# 02_LP_FMC.net
KiCad netlist of a schematic drawn in Altium Designer
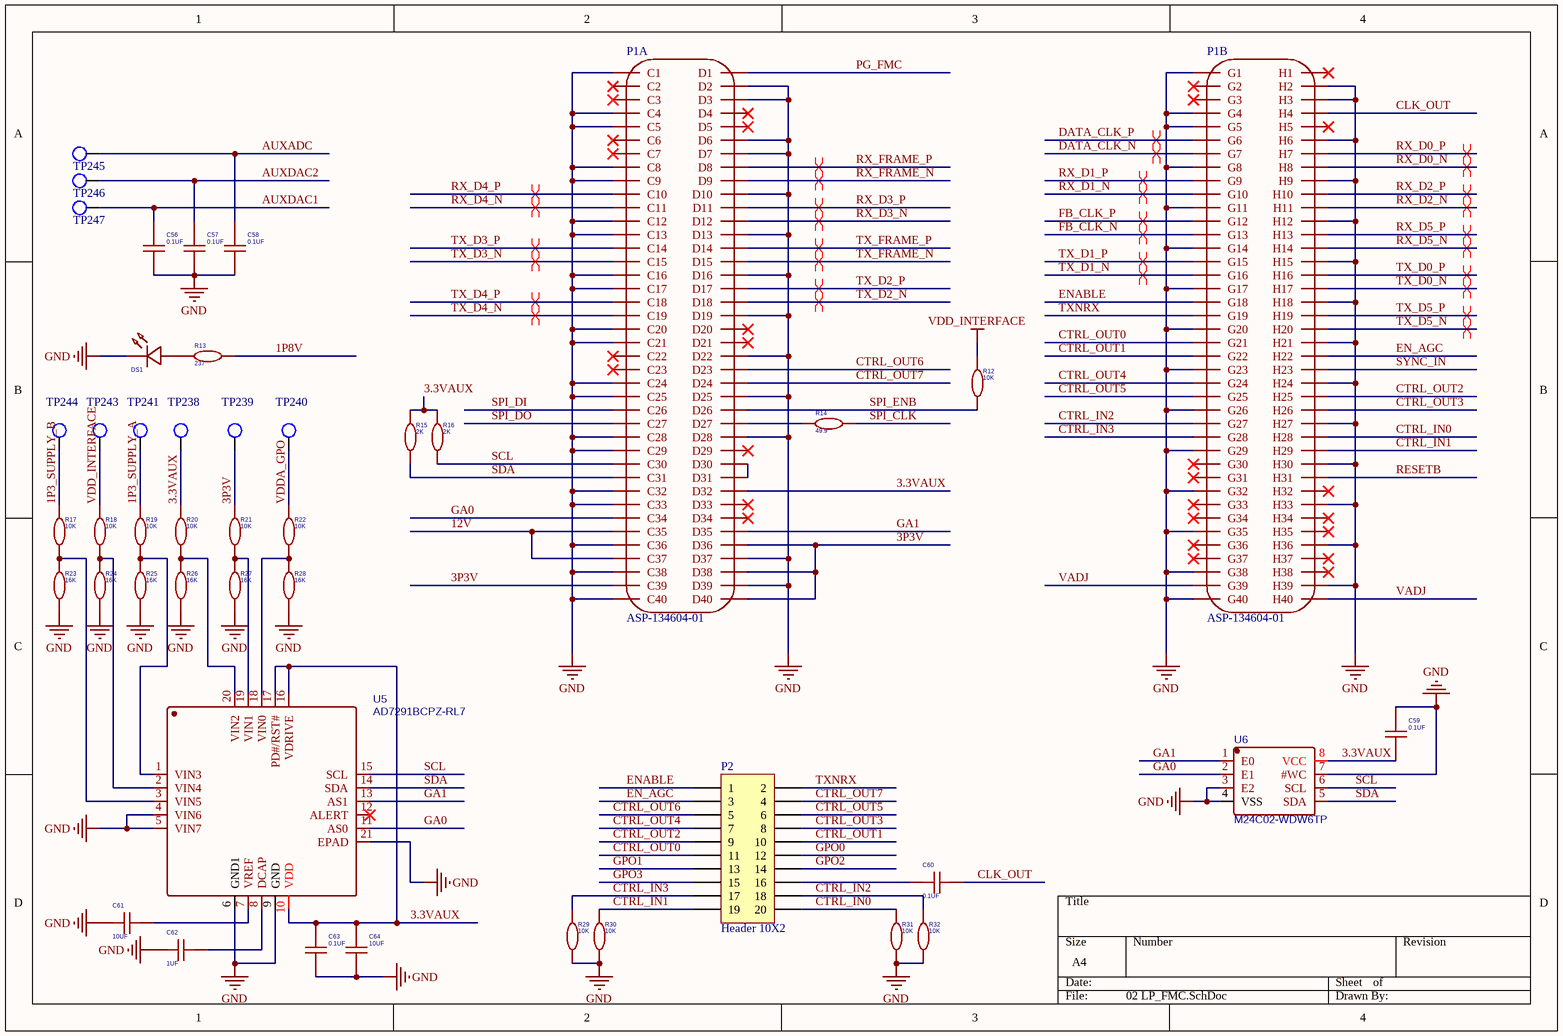
[diagram p0: 02 LP_FMC.SchDoc]

(export (version "E")
  (design (tool "Eeschema 10.0.6"))
  (components
    (comp (ref "C56")
      (value "0.1UF")
      (footprint "C0201")
      (fields
        (field (name "BOM_MANUFACTURER PART") "0402B104K160")
        (field (name "BOM_SUPPLIER PART") "C83056")
      )
      (libsource (lib "pluto-7020CLG400") (part "0.1UF"))
    )
    (comp (ref "C57")
      (value "0.1UF")
      (footprint "C0402")
      (fields
        (field (name "BOM_MANUFACTURER PART") "0402B104K160")
        (field (name "BOM_SUPPLIER PART") "C83056")
      )
      (libsource (lib "pluto-7020CLG400") (part "0.1UF"))
    )
    (comp (ref "C58")
      (value "0.1UF")
      (footprint "C0201")
      (fields
        (field (name "BOM_MANUFACTURER PART") "0402B104K160")
        (field (name "BOM_SUPPLIER PART") "C83056")
      )
      (libsource (lib "pluto-7020CLG400") (part "0.1UF"))
    )
    (comp (ref "C59")
      (value "0.1UF")
      (footprint "C0402")
      (fields
        (field (name "BOM_MANUFACTURER PART") "0402B104K160")
        (field (name "BOM_SUPPLIER PART") "C83056")
      )
      (libsource (lib "pluto-7020CLG400") (part "0.1UF"))
    )
    (comp (ref "C60")
      (value "0.1UF")
      (footprint "C0402")
      (fields
        (field (name "BOM_MANUFACTURER PART") "0402B104K160")
        (field (name "BOM_SUPPLIER PART") "C83056")
      )
      (libsource (lib "pluto-7020CLG400") (part "0.1UF"))
    )
    (comp (ref "C61")
      (value "10UF")
      (footprint "C0402")
      (fields
        (field (name "BOM_MANUFACTURER PART") "0402B104K160")
        (field (name "BOM_SUPPLIER PART") "C83056")
      )
      (libsource (lib "pluto-7020CLG400") (part "10UF"))
    )
    (comp (ref "C62")
      (value "1UF")
      (footprint "C0402")
      (fields
        (field (name "BOM_MANUFACTURER PART") "0402B104K160")
        (field (name "BOM_SUPPLIER PART") "C83056")
      )
      (libsource (lib "pluto-7020CLG400") (part "0.1UF"))
    )
    (comp (ref "C63")
      (value "0.1UF")
      (footprint "C0201")
      (fields
        (field (name "BOM_MANUFACTURER PART") "0402B104K160")
        (field (name "BOM_SUPPLIER PART") "C83056")
      )
      (libsource (lib "pluto-7020CLG400") (part "0.1UF"))
    )
    (comp (ref "C64")
      (value "10UF")
      (footprint "C0402")
      (fields
        (field (name "BOM_MANUFACTURER PART") "0402B104K160")
        (field (name "BOM_SUPPLIER PART") "C83056")
      )
      (libsource (lib "pluto-7020CLG400") (part "10UF"))
    )
    (comp (ref "DS1")
      (value "16-213SURC/S530-A3/TR8")
      (footprint "LED0805-RD")
      (fields (field (name "BOM_SUPPLIER PART") "C605452") (field (name "CONTRIBUTOR") "LCSC"))
      (libsource (lib "pluto-7020CLG400") (part "16-213SURC/S530-A3/TR8"))
    )
    (comp (ref "P1")
      (value "ASP-134604-01")
      (footprint "CNSAMTECASP-134604-01")
      (libsource (lib "FMCOMMS3_compatible_board") (part "ASP-134604-01"))
    )
    (comp (ref "P2")
      (value "Header 10X2")
      (footprint "CNBERGF2X10H335LD32")
      (description "Header, 10-Pin, Dual row")
      (fields (field (name "PUBLISHER") "Altium Limited"))
      (libsource (lib "Miscellaneous Connectors") (part "Header 10X2"))
    )
    (comp (ref "R12")
      (value "10K")
      (footprint "C0201")
      (fields
        (field (name "BOM_SUPPLIER PART") "C185392")
        (field (name "BOM_MANUFACTURER PART") "RC0402FR-0780R6L")
        (field (name "CONTRIBUTOR") "LCSC")
      )
      (libsource (lib "pluto-7020CLG400") (part "10K"))
    )
    (comp (ref "R13")
      (value "237")
      (footprint "LC-0402_R")
      (fields
        (field (name "BOM_SUPPLIER PART") "C185392")
        (field (name "BOM_MANUFACTURER PART") "RC0402FR-0780R6L")
        (field (name "CONTRIBUTOR") "LCSC")
      )
      (libsource (lib "pluto-7020CLG400") (part "10R"))
    )
    (comp (ref "R14")
      (value "49.9")
      (footprint "C0201")
      (fields
        (field (name "BOM_SUPPLIER PART") "C185392")
        (field (name "BOM_MANUFACTURER PART") "RC0402FR-0780R6L")
        (field (name "CONTRIBUTOR") "LCSC")
      )
      (libsource (lib "pluto-7020CLG400") (part "39"))
    )
    (comp (ref "R15")
      (value "2K")
      (footprint "C0201")
      (fields
        (field (name "BOM_SUPPLIER PART") "C185392")
        (field (name "BOM_MANUFACTURER PART") "RC0402FR-0780R6L")
        (field (name "CONTRIBUTOR") "LCSC")
      )
      (libsource (lib "pluto-7020CLG400") (part "1K"))
    )
    (comp (ref "R16")
      (value "2K")
      (footprint "C0201")
      (fields
        (field (name "BOM_SUPPLIER PART") "C185392")
        (field (name "BOM_MANUFACTURER PART") "RC0402FR-0780R6L")
        (field (name "CONTRIBUTOR") "LCSC")
      )
      (libsource (lib "pluto-7020CLG400") (part "1K"))
    )
    (comp (ref "R17")
      (value "10K")
      (footprint "C0201")
      (fields
        (field (name "BOM_SUPPLIER PART") "C185392")
        (field (name "BOM_MANUFACTURER PART") "RC0402FR-0780R6L")
        (field (name "CONTRIBUTOR") "LCSC")
      )
      (libsource (lib "pluto-7020CLG400") (part "10K"))
    )
    (comp (ref "R18")
      (value "10K")
      (footprint "C0201")
      (fields
        (field (name "BOM_SUPPLIER PART") "C185392")
        (field (name "BOM_MANUFACTURER PART") "RC0402FR-0780R6L")
        (field (name "CONTRIBUTOR") "LCSC")
      )
      (libsource (lib "pluto-7020CLG400") (part "10K"))
    )
    (comp (ref "R19")
      (value "10K")
      (footprint "C0201")
      (fields
        (field (name "BOM_SUPPLIER PART") "C185392")
        (field (name "BOM_MANUFACTURER PART") "RC0402FR-0780R6L")
        (field (name "CONTRIBUTOR") "LCSC")
      )
      (libsource (lib "pluto-7020CLG400") (part "10K"))
    )
    (comp (ref "R20")
      (value "10K")
      (footprint "C0201")
      (fields
        (field (name "BOM_SUPPLIER PART") "C185392")
        (field (name "BOM_MANUFACTURER PART") "RC0402FR-0780R6L")
        (field (name "CONTRIBUTOR") "LCSC")
      )
      (libsource (lib "pluto-7020CLG400") (part "10K"))
    )
    (comp (ref "R21")
      (value "10K")
      (footprint "C0201")
      (fields
        (field (name "BOM_SUPPLIER PART") "C185392")
        (field (name "BOM_MANUFACTURER PART") "RC0402FR-0780R6L")
        (field (name "CONTRIBUTOR") "LCSC")
      )
      (libsource (lib "pluto-7020CLG400") (part "10K"))
    )
    (comp (ref "R22")
      (value "10K")
      (footprint "C0201")
      (fields
        (field (name "BOM_SUPPLIER PART") "C185392")
        (field (name "BOM_MANUFACTURER PART") "RC0402FR-0780R6L")
        (field (name "CONTRIBUTOR") "LCSC")
      )
      (libsource (lib "pluto-7020CLG400") (part "10K"))
    )
    (comp (ref "R23")
      (value "16K")
      (footprint "C0201")
      (fields
        (field (name "BOM_SUPPLIER PART") "C185392")
        (field (name "BOM_MANUFACTURER PART") "RC0402FR-0780R6L")
        (field (name "CONTRIBUTOR") "LCSC")
      )
      (libsource (lib "pluto-7020CLG400") (part "10K"))
    )
    (comp (ref "R24")
      (value "16K")
      (footprint "C0201")
      (fields
        (field (name "BOM_SUPPLIER PART") "C185392")
        (field (name "BOM_MANUFACTURER PART") "RC0402FR-0780R6L")
        (field (name "CONTRIBUTOR") "LCSC")
      )
      (libsource (lib "pluto-7020CLG400") (part "10K"))
    )
    (comp (ref "R25")
      (value "16K")
      (footprint "C0201")
      (fields
        (field (name "BOM_SUPPLIER PART") "C185392")
        (field (name "BOM_MANUFACTURER PART") "RC0402FR-0780R6L")
        (field (name "CONTRIBUTOR") "LCSC")
      )
      (libsource (lib "pluto-7020CLG400") (part "10K"))
    )
    (comp (ref "R26")
      (value "16K")
      (footprint "C0201")
      (fields
        (field (name "BOM_SUPPLIER PART") "C185392")
        (field (name "BOM_MANUFACTURER PART") "RC0402FR-0780R6L")
        (field (name "CONTRIBUTOR") "LCSC")
      )
      (libsource (lib "pluto-7020CLG400") (part "10K"))
    )
    (comp (ref "R27")
      (value "16K")
      (footprint "C0201")
      (fields
        (field (name "BOM_SUPPLIER PART") "C185392")
        (field (name "BOM_MANUFACTURER PART") "RC0402FR-0780R6L")
        (field (name "CONTRIBUTOR") "LCSC")
      )
      (libsource (lib "pluto-7020CLG400") (part "10K"))
    )
    (comp (ref "R28")
      (value "16K")
      (footprint "C0201")
      (fields
        (field (name "BOM_SUPPLIER PART") "C185392")
        (field (name "BOM_MANUFACTURER PART") "RC0402FR-0780R6L")
        (field (name "CONTRIBUTOR") "LCSC")
      )
      (libsource (lib "pluto-7020CLG400") (part "10K"))
    )
    (comp (ref "R29")
      (value "10K")
      (footprint "C0201")
      (fields
        (field (name "BOM_SUPPLIER PART") "C185392")
        (field (name "BOM_MANUFACTURER PART") "RC0402FR-0780R6L")
        (field (name "CONTRIBUTOR") "LCSC")
      )
      (libsource (lib "pluto-7020CLG400") (part "10K"))
    )
    (comp (ref "R30")
      (value "10K")
      (footprint "C0201")
      (fields
        (field (name "BOM_SUPPLIER PART") "C185392")
        (field (name "BOM_MANUFACTURER PART") "RC0402FR-0780R6L")
        (field (name "CONTRIBUTOR") "LCSC")
      )
      (libsource (lib "pluto-7020CLG400") (part "10K"))
    )
    (comp (ref "R31")
      (value "10K")
      (footprint "C0201")
      (fields
        (field (name "BOM_SUPPLIER PART") "C185392")
        (field (name "BOM_MANUFACTURER PART") "RC0402FR-0780R6L")
        (field (name "CONTRIBUTOR") "LCSC")
      )
      (libsource (lib "pluto-7020CLG400") (part "10K"))
    )
    (comp (ref "R32")
      (value "10K")
      (footprint "C0201")
      (fields
        (field (name "BOM_SUPPLIER PART") "C185392")
        (field (name "BOM_MANUFACTURER PART") "RC0402FR-0780R6L")
        (field (name "CONTRIBUTOR") "LCSC")
      )
      (libsource (lib "pluto-7020CLG400") (part "10K"))
    )
    (comp (ref "TP238")
      (value "TEST POINT SURFACE")
      (footprint "TPC75D45")
      (libsource (lib "Allwinner_H6_Core") (part "TEST POINT SURFACE_1"))
    )
    (comp (ref "TP239")
      (value "TEST POINT SURFACE")
      (footprint "TPC75D45")
      (libsource (lib "Allwinner_H6_Core") (part "TEST POINT SURFACE_1"))
    )
    (comp (ref "TP240")
      (value "TEST POINT SURFACE")
      (footprint "TPC75D45")
      (libsource (lib "Allwinner_H6_Core") (part "TEST POINT SURFACE_1"))
    )
    (comp (ref "TP241")
      (value "TEST POINT SURFACE")
      (footprint "TPC75D45")
      (libsource (lib "Allwinner_H6_Core") (part "TEST POINT SURFACE_1"))
    )
    (comp (ref "TP243")
      (value "TEST POINT SURFACE")
      (footprint "TPC75D45")
      (libsource (lib "Allwinner_H6_Core") (part "TEST POINT SURFACE_1"))
    )
    (comp (ref "TP244")
      (value "TEST POINT SURFACE")
      (footprint "TPC75D45")
      (libsource (lib "Allwinner_H6_Core") (part "TEST POINT SURFACE_1"))
    )
    (comp (ref "TP245")
      (value "TEST POINT SURFACE")
      (footprint "TPC75D45")
      (libsource (lib "Allwinner_H6_Core") (part "TEST POINT SURFACE_1"))
    )
    (comp (ref "TP246")
      (value "TEST POINT SURFACE")
      (footprint "TPC75D45")
      (libsource (lib "Allwinner_H6_Core") (part "TEST POINT SURFACE_1"))
    )
    (comp (ref "TP247")
      (value "TEST POINT SURFACE")
      (footprint "TPC75D45")
      (libsource (lib "Allwinner_H6_Core") (part "TEST POINT SURFACE_1"))
    )
    (comp (ref "U5")
      (value "AD7291BCPZ-RL7")
      (footprint "LFCSP-20_L4.0-W4.0-P0.50-TL-EP2.7")
      (fields (field (name "BOM_SUPPLIER PART") "C207434") (field (name "CONTRIBUTOR") "LCSC"))
      (libsource (lib "demo_fmccomms3") (part "AD7291BCPZ-RL7"))
    )
    (comp (ref "U6")
      (value "M24C02-WDW6TP")
      (footprint "TSSOP8")
      (fields (field (name "BOM_SUPPLIER PART") "C283436") (field (name "CONTRIBUTOR") "LCSC"))
      (libsource (lib "demo_fmccomms3") (part "M24C02-WDW6TP"))
    )
  )
  (nets
    (net (code "1") (name "/1P3_SUPPLY_A") (class "Default")
      (node (ref "R19") (pin "1") (pinfunction "1_1") (pintype "passive"))
      (node (ref "TP241") (pin "1") (pinfunction "TP_1") (pintype "passive"))
    )
    (net (code "2") (name "/1P3_SUPPLY_B") (class "Default")
      (node (ref "R17") (pin "1") (pinfunction "1_1") (pintype "passive"))
      (node (ref "TP244") (pin "1") (pinfunction "TP_1") (pintype "passive"))
    )
    (net (code "3") (name "/1P8V") (class "Default")
      (node (ref "R13") (pin "2") (pinfunction "2_2") (pintype "passive"))
    )
    (net (code "4") (name "/3.3VAUX") (class "Default")
      (node (ref "C59") (pin "2") (pinfunction "2_2") (pintype "passive"))
      (node (ref "C63") (pin "1") (pinfunction "1_1") (pintype "passive"))
      (node (ref "C64") (pin "1") (pinfunction "1_1") (pintype "passive"))
      (node (ref "P1") (pin "D32") (pinfunction "D32_D32") (pintype "passive"))
      (node (ref "R15") (pin "2") (pinfunction "2_2") (pintype "passive"))
      (node (ref "R16") (pin "2") (pinfunction "2_2") (pintype "passive"))
      (node (ref "R20") (pin "1") (pinfunction "1_1") (pintype "passive"))
      (node (ref "TP238") (pin "1") (pinfunction "TP_1") (pintype "passive"))
      (node (ref "U5") (pin "10") (pinfunction "VDD_10") (pintype "passive"))
      (node (ref "U5") (pin "16") (pinfunction "VDRIVE_16") (pintype "passive"))
      (node (ref "U5") (pin "17") (pinfunction "PD#/RST#_17") (pintype "passive"))
      (node (ref "U6") (pin "8") (pinfunction "VCC_8") (pintype "passive"))
    )
    (net (code "5") (name "/3P3V") (class "Default")
      (node (ref "P1") (pin "C39") (pinfunction "C39_C39") (pintype "passive"))
      (node (ref "P1") (pin "D36") (pinfunction "D36_D36") (pintype "passive"))
      (node (ref "P1") (pin "D38") (pinfunction "D38_D38") (pintype "passive"))
      (node (ref "P1") (pin "D40") (pinfunction "D40_D40") (pintype "passive"))
      (node (ref "R21") (pin "1") (pinfunction "1_1") (pintype "passive"))
      (node (ref "TP239") (pin "1") (pinfunction "TP_1") (pintype "passive"))
    )
    (net (code "6") (name "/12V") (class "Default")
      (node (ref "P1") (pin "C35") (pinfunction "C35_C35") (pintype "passive"))
      (node (ref "P1") (pin "C37") (pinfunction "C37_C37") (pintype "passive"))
    )
    (net (code "7") (name "/AUXADC") (class "Default")
      (node (ref "C58") (pin "1") (pinfunction "1_1") (pintype "passive"))
      (node (ref "TP245") (pin "1") (pinfunction "TP_1") (pintype "passive"))
    )
    (net (code "8") (name "/AUXDAC1") (class "Default")
      (node (ref "C56") (pin "1") (pinfunction "1_1") (pintype "passive"))
      (node (ref "TP247") (pin "1") (pinfunction "TP_1") (pintype "passive"))
    )
    (net (code "9") (name "/AUXDAC2") (class "Default")
      (node (ref "C57") (pin "1") (pinfunction "1_1") (pintype "passive"))
      (node (ref "TP246") (pin "1") (pinfunction "TP_1") (pintype "passive"))
    )
    (net (code "10") (name "/CLK_OUT") (class "Default")
      (node (ref "C60") (pin "2") (pinfunction "2_2") (pintype "passive"))
      (node (ref "P1") (pin "H4") (pinfunction "H4_H4") (pintype "passive"))
    )
    (net (code "11") (name "/CTRL_IN0") (class "Default")
      (node (ref "P1") (pin "H28") (pinfunction "H28_H28") (pintype "passive"))
      (node (ref "P2") (pin "20") (pinfunction "20_20") (pintype "passive"))
      (node (ref "R31") (pin "2") (pinfunction "2_2") (pintype "passive"))
    )
    (net (code "12") (name "/CTRL_IN1") (class "Default")
      (node (ref "P1") (pin "H29") (pinfunction "H29_H29") (pintype "passive"))
      (node (ref "P2") (pin "19") (pinfunction "19_19") (pintype "passive"))
      (node (ref "R30") (pin "2") (pinfunction "2_2") (pintype "passive"))
    )
    (net (code "13") (name "/CTRL_IN2") (class "Default")
      (node (ref "P1") (pin "G27") (pinfunction "G27_G27") (pintype "passive"))
      (node (ref "P2") (pin "18") (pinfunction "18_18") (pintype "passive"))
      (node (ref "R32") (pin "2") (pinfunction "2_2") (pintype "passive"))
    )
    (net (code "14") (name "/CTRL_IN3") (class "Default")
      (node (ref "P1") (pin "G28") (pinfunction "G28_G28") (pintype "passive"))
      (node (ref "P2") (pin "17") (pinfunction "17_17") (pintype "passive"))
      (node (ref "R29") (pin "2") (pinfunction "2_2") (pintype "passive"))
    )
    (net (code "15") (name "/CTRL_OUT0") (class "Default")
      (node (ref "P1") (pin "G21") (pinfunction "G21_G21") (pintype "passive"))
      (node (ref "P2") (pin "11") (pinfunction "11_11") (pintype "passive"))
    )
    (net (code "16") (name "/CTRL_OUT1") (class "Default")
      (node (ref "P1") (pin "G22") (pinfunction "G22_G22") (pintype "passive"))
      (node (ref "P2") (pin "10") (pinfunction "10_10") (pintype "passive"))
    )
    (net (code "17") (name "/CTRL_OUT2") (class "Default")
      (node (ref "P1") (pin "H25") (pinfunction "H25_H25") (pintype "passive"))
      (node (ref "P2") (pin "9") (pinfunction "9_9") (pintype "passive"))
    )
    (net (code "18") (name "/CTRL_OUT3") (class "Default")
      (node (ref "P1") (pin "H26") (pinfunction "H26_H26") (pintype "passive"))
      (node (ref "P2") (pin "8") (pinfunction "8_8") (pintype "passive"))
    )
    (net (code "19") (name "/CTRL_OUT4") (class "Default")
      (node (ref "P1") (pin "G24") (pinfunction "G24_G24") (pintype "passive"))
      (node (ref "P2") (pin "7") (pinfunction "7_7") (pintype "passive"))
    )
    (net (code "20") (name "/CTRL_OUT5") (class "Default")
      (node (ref "P1") (pin "G25") (pinfunction "G25_G25") (pintype "passive"))
      (node (ref "P2") (pin "6") (pinfunction "6_6") (pintype "passive"))
    )
    (net (code "21") (name "/CTRL_OUT6") (class "Default")
      (node (ref "P1") (pin "D23") (pinfunction "D23_D23") (pintype "passive"))
      (node (ref "P2") (pin "5") (pinfunction "5_5") (pintype "passive"))
    )
    (net (code "22") (name "/CTRL_OUT7") (class "Default")
      (node (ref "P1") (pin "D24") (pinfunction "D24_D24") (pintype "passive"))
      (node (ref "P2") (pin "4") (pinfunction "4_4") (pintype "passive"))
    )
    (net (code "23") (name "/DATA_CLK_N") (class "Default")
      (node (ref "P1") (pin "G7") (pinfunction "G7_G7") (pintype "passive"))
    )
    (net (code "24") (name "/DATA_CLK_P") (class "Default")
      (node (ref "P1") (pin "G6") (pinfunction "G6_G6") (pintype "passive"))
    )
    (net (code "25") (name "/ENABLE") (class "Default")
      (node (ref "P1") (pin "G18") (pinfunction "G18_G18") (pintype "passive"))
      (node (ref "P2") (pin "1") (pinfunction "1_1") (pintype "passive"))
    )
    (net (code "26") (name "/EN_AGC") (class "Default")
      (node (ref "P1") (pin "H22") (pinfunction "H22_H22") (pintype "passive"))
      (node (ref "P2") (pin "3") (pinfunction "3_3") (pintype "passive"))
    )
    (net (code "27") (name "/FB_CLK_N") (class "Default")
      (node (ref "P1") (pin "G13") (pinfunction "G13_G13") (pintype "passive"))
    )
    (net (code "28") (name "/FB_CLK_P") (class "Default")
      (node (ref "P1") (pin "G12") (pinfunction "G12_G12") (pintype "passive"))
    )
    (net (code "29") (name "/GA0") (class "Default")
      (node (ref "P1") (pin "C34") (pinfunction "C34_C34") (pintype "passive"))
      (node (ref "U5") (pin "11") (pinfunction "AS0_11") (pintype "passive"))
      (node (ref "U6") (pin "2") (pinfunction "E1_2") (pintype "passive"))
    )
    (net (code "30") (name "/GA1") (class "Default")
      (node (ref "P1") (pin "D35") (pinfunction "D35_D35") (pintype "passive"))
      (node (ref "U5") (pin "13") (pinfunction "AS1_13") (pintype "passive"))
      (node (ref "U6") (pin "1") (pinfunction "E0_1") (pintype "passive"))
    )
    (net (code "31") (name "/GPO0") (class "Default")
      (node (ref "P2") (pin "12") (pinfunction "12_12") (pintype "passive"))
    )
    (net (code "32") (name "/GPO1") (class "Default")
      (node (ref "P2") (pin "13") (pinfunction "13_13") (pintype "passive"))
    )
    (net (code "33") (name "/GPO2") (class "Default")
      (node (ref "P2") (pin "14") (pinfunction "14_14") (pintype "passive"))
    )
    (net (code "34") (name "/GPO3") (class "Default")
      (node (ref "P2") (pin "15") (pinfunction "15_15") (pintype "passive"))
    )
    (net (code "35") (name "/PG_FMC") (class "Default")
      (node (ref "P1") (pin "D1") (pinfunction "D1_D1") (pintype "passive"))
    )
    (net (code "36") (name "/RESETB") (class "Default")
      (node (ref "P1") (pin "H31") (pinfunction "H31_H31") (pintype "passive"))
    )
    (net (code "37") (name "/RX_D0_N") (class "Default")
      (node (ref "P1") (pin "H8") (pinfunction "H8_H8") (pintype "passive"))
    )
    (net (code "38") (name "/RX_D0_P") (class "Default")
      (node (ref "P1") (pin "H7") (pinfunction "H7_H7") (pintype "passive"))
    )
    (net (code "39") (name "/RX_D1_N") (class "Default")
      (node (ref "P1") (pin "G10") (pinfunction "G10_G10") (pintype "passive"))
    )
    (net (code "40") (name "/RX_D1_P") (class "Default")
      (node (ref "P1") (pin "G9") (pinfunction "G9_G9") (pintype "passive"))
    )
    (net (code "41") (name "/RX_D2_N") (class "Default")
      (node (ref "P1") (pin "H11") (pinfunction "H11_H11") (pintype "passive"))
    )
    (net (code "42") (name "/RX_D2_P") (class "Default")
      (node (ref "P1") (pin "H10") (pinfunction "H10_H10") (pintype "passive"))
    )
    (net (code "43") (name "/RX_D3_N") (class "Default")
      (node (ref "P1") (pin "D12") (pinfunction "D12_D12") (pintype "passive"))
    )
    (net (code "44") (name "/RX_D3_P") (class "Default")
      (node (ref "P1") (pin "D11") (pinfunction "D11_D11") (pintype "passive"))
    )
    (net (code "45") (name "/RX_D4_N") (class "Default")
      (node (ref "P1") (pin "C11") (pinfunction "C11_C11") (pintype "passive"))
    )
    (net (code "46") (name "/RX_D4_P") (class "Default")
      (node (ref "P1") (pin "C10") (pinfunction "C10_C10") (pintype "passive"))
    )
    (net (code "47") (name "/RX_D5_N") (class "Default")
      (node (ref "P1") (pin "H14") (pinfunction "H14_H14") (pintype "passive"))
    )
    (net (code "48") (name "/RX_D5_P") (class "Default")
      (node (ref "P1") (pin "H13") (pinfunction "H13_H13") (pintype "passive"))
    )
    (net (code "49") (name "/RX_FRAME_N") (class "Default")
      (node (ref "P1") (pin "D9") (pinfunction "D9_D9") (pintype "passive"))
    )
    (net (code "50") (name "/RX_FRAME_P") (class "Default")
      (node (ref "P1") (pin "D8") (pinfunction "D8_D8") (pintype "passive"))
    )
    (net (code "51") (name "/SCL") (class "Default")
      (node (ref "P1") (pin "C30") (pinfunction "C30_C30") (pintype "passive"))
      (node (ref "R16") (pin "1") (pinfunction "1_1") (pintype "passive"))
      (node (ref "U5") (pin "15") (pinfunction "SCL_15") (pintype "passive"))
      (node (ref "U6") (pin "6") (pinfunction "SCL_6") (pintype "passive"))
    )
    (net (code "52") (name "/SDA") (class "Default")
      (node (ref "P1") (pin "C31") (pinfunction "C31_C31") (pintype "passive"))
      (node (ref "R15") (pin "1") (pinfunction "1_1") (pintype "passive"))
      (node (ref "U5") (pin "14") (pinfunction "SDA_14") (pintype "passive"))
      (node (ref "U6") (pin "5") (pinfunction "SDA_5") (pintype "passive"))
    )
    (net (code "53") (name "/SPI_CLK") (class "Default")
      (node (ref "R14") (pin "2") (pinfunction "2_2") (pintype "passive"))
    )
    (net (code "54") (name "/SPI_DI") (class "Default")
      (node (ref "P1") (pin "C26") (pinfunction "C26_C26") (pintype "passive"))
    )
    (net (code "55") (name "/SPI_DO") (class "Default")
      (node (ref "P1") (pin "C27") (pinfunction "C27_C27") (pintype "passive"))
    )
    (net (code "56") (name "/SPI_ENB") (class "Default")
      (node (ref "P1") (pin "D26") (pinfunction "D26_D26") (pintype "passive"))
      (node (ref "R12") (pin "1") (pinfunction "1_1") (pintype "passive"))
    )
    (net (code "57") (name "/SYNC_IN") (class "Default")
      (node (ref "P1") (pin "H23") (pinfunction "H23_H23") (pintype "passive"))
    )
    (net (code "58") (name "/TXNRX") (class "Default")
      (node (ref "P1") (pin "G19") (pinfunction "G19_G19") (pintype "passive"))
      (node (ref "P2") (pin "2") (pinfunction "2_2") (pintype "passive"))
    )
    (net (code "59") (name "/TX_D0_N") (class "Default")
      (node (ref "P1") (pin "H17") (pinfunction "H17_H17") (pintype "passive"))
    )
    (net (code "60") (name "/TX_D0_P") (class "Default")
      (node (ref "P1") (pin "H16") (pinfunction "H16_H16") (pintype "passive"))
    )
    (net (code "61") (name "/TX_D1_N") (class "Default")
      (node (ref "P1") (pin "G16") (pinfunction "G16_G16") (pintype "passive"))
    )
    (net (code "62") (name "/TX_D1_P") (class "Default")
      (node (ref "P1") (pin "G15") (pinfunction "G15_G15") (pintype "passive"))
    )
    (net (code "63") (name "/TX_D2_N") (class "Default")
      (node (ref "P1") (pin "D18") (pinfunction "D18_D18") (pintype "passive"))
    )
    (net (code "64") (name "/TX_D2_P") (class "Default")
      (node (ref "P1") (pin "D17") (pinfunction "D17_D17") (pintype "passive"))
    )
    (net (code "65") (name "/TX_D3_N") (class "Default")
      (node (ref "P1") (pin "C15") (pinfunction "C15_C15") (pintype "passive"))
    )
    (net (code "66") (name "/TX_D3_P") (class "Default")
      (node (ref "P1") (pin "C14") (pinfunction "C14_C14") (pintype "passive"))
    )
    (net (code "67") (name "/TX_D4_N") (class "Default")
      (node (ref "P1") (pin "C19") (pinfunction "C19_C19") (pintype "passive"))
    )
    (net (code "68") (name "/TX_D4_P") (class "Default")
      (node (ref "P1") (pin "C18") (pinfunction "C18_C18") (pintype "passive"))
    )
    (net (code "69") (name "/TX_D5_N") (class "Default")
      (node (ref "P1") (pin "H20") (pinfunction "H20_H20") (pintype "passive"))
    )
    (net (code "70") (name "/TX_D5_P") (class "Default")
      (node (ref "P1") (pin "H19") (pinfunction "H19_H19") (pintype "passive"))
    )
    (net (code "71") (name "/TX_FRAME_N") (class "Default")
      (node (ref "P1") (pin "D15") (pinfunction "D15_D15") (pintype "passive"))
    )
    (net (code "72") (name "/TX_FRAME_P") (class "Default")
      (node (ref "P1") (pin "D14") (pinfunction "D14_D14") (pintype "passive"))
    )
    (net (code "73") (name "/VADJ") (class "Default")
      (node (ref "P1") (pin "G39") (pinfunction "G39_G39") (pintype "passive"))
      (node (ref "P1") (pin "H40") (pinfunction "H40_H40") (pintype "passive"))
    )
    (net (code "74") (name "/VDDA_GPO") (class "Default")
      (node (ref "R22") (pin "1") (pinfunction "1_1") (pintype "passive"))
      (node (ref "TP240") (pin "1") (pinfunction "TP_1") (pintype "passive"))
    )
    (net (code "75") (name "GND") (class "Default")
      (node (ref "C56") (pin "2") (pinfunction "2_2") (pintype "passive"))
      (node (ref "C57") (pin "2") (pinfunction "2_2") (pintype "passive"))
      (node (ref "C58") (pin "2") (pinfunction "2_2") (pintype "passive"))
      (node (ref "C59") (pin "1") (pinfunction "1_1") (pintype "passive"))
      (node (ref "C61") (pin "1") (pinfunction "1_1") (pintype "passive"))
      (node (ref "C62") (pin "2") (pinfunction "2_2") (pintype "passive"))
      (node (ref "C63") (pin "2") (pinfunction "2_2") (pintype "passive"))
      (node (ref "C64") (pin "2") (pinfunction "2_2") (pintype "passive"))
      (node (ref "DS1") (pin "1") (pinfunction "-_1") (pintype "passive"))
      (node (ref "P1") (pin "C1") (pinfunction "C1_C1") (pintype "passive"))
      (node (ref "P1") (pin "C12") (pinfunction "C12_C12") (pintype "passive"))
      (node (ref "P1") (pin "C13") (pinfunction "C13_C13") (pintype "passive"))
      (node (ref "P1") (pin "C16") (pinfunction "C16_C16") (pintype "passive"))
      (node (ref "P1") (pin "C17") (pinfunction "C17_C17") (pintype "passive"))
      (node (ref "P1") (pin "C20") (pinfunction "C20_C20") (pintype "passive"))
      (node (ref "P1") (pin "C21") (pinfunction "C21_C21") (pintype "passive"))
      (node (ref "P1") (pin "C24") (pinfunction "C24_C24") (pintype "passive"))
      (node (ref "P1") (pin "C25") (pinfunction "C25_C25") (pintype "passive"))
      (node (ref "P1") (pin "C28") (pinfunction "C28_C28") (pintype "passive"))
      (node (ref "P1") (pin "C29") (pinfunction "C29_C29") (pintype "passive"))
      (node (ref "P1") (pin "C32") (pinfunction "C32_C32") (pintype "passive"))
      (node (ref "P1") (pin "C33") (pinfunction "C33_C33") (pintype "passive"))
      (node (ref "P1") (pin "C36") (pinfunction "C36_C36") (pintype "passive"))
      (node (ref "P1") (pin "C38") (pinfunction "C38_C38") (pintype "passive"))
      (node (ref "P1") (pin "C4") (pinfunction "C4_C4") (pintype "passive"))
      (node (ref "P1") (pin "C40") (pinfunction "C40_C40") (pintype "passive"))
      (node (ref "P1") (pin "C5") (pinfunction "C5_C5") (pintype "passive"))
      (node (ref "P1") (pin "C8") (pinfunction "C8_C8") (pintype "passive"))
      (node (ref "P1") (pin "C9") (pinfunction "C9_C9") (pintype "passive"))
      (node (ref "P1") (pin "D10") (pinfunction "D10_D10") (pintype "passive"))
      (node (ref "P1") (pin "D13") (pinfunction "D13_D13") (pintype "passive"))
      (node (ref "P1") (pin "D16") (pinfunction "D16_D16") (pintype "passive"))
      (node (ref "P1") (pin "D19") (pinfunction "D19_D19") (pintype "passive"))
      (node (ref "P1") (pin "D2") (pinfunction "D2_D2") (pintype "passive"))
      (node (ref "P1") (pin "D22") (pinfunction "D22_D22") (pintype "passive"))
      (node (ref "P1") (pin "D25") (pinfunction "D25_D25") (pintype "passive"))
      (node (ref "P1") (pin "D28") (pinfunction "D28_D28") (pintype "passive"))
      (node (ref "P1") (pin "D3") (pinfunction "D3_D3") (pintype "passive"))
      (node (ref "P1") (pin "D37") (pinfunction "D37_D37") (pintype "passive"))
      (node (ref "P1") (pin "D39") (pinfunction "D39_D39") (pintype "passive"))
      (node (ref "P1") (pin "D6") (pinfunction "D6_D6") (pintype "passive"))
      (node (ref "P1") (pin "D7") (pinfunction "D7_D7") (pintype "passive"))
      (node (ref "P1") (pin "G1") (pinfunction "G1_G1") (pintype "passive"))
      (node (ref "P1") (pin "G11") (pinfunction "G11_G11") (pintype "passive"))
      (node (ref "P1") (pin "G14") (pinfunction "G14_G14") (pintype "passive"))
      (node (ref "P1") (pin "G17") (pinfunction "G17_G17") (pintype "passive"))
      (node (ref "P1") (pin "G20") (pinfunction "G20_G20") (pintype "passive"))
      (node (ref "P1") (pin "G23") (pinfunction "G23_G23") (pintype "passive"))
      (node (ref "P1") (pin "G26") (pinfunction "G26_G26") (pintype "passive"))
      (node (ref "P1") (pin "G29") (pinfunction "G29_G29") (pintype "passive"))
      (node (ref "P1") (pin "G32") (pinfunction "G32_G32") (pintype "passive"))
      (node (ref "P1") (pin "G35") (pinfunction "G35_G35") (pintype "passive"))
      (node (ref "P1") (pin "G38") (pinfunction "G38_G38") (pintype "passive"))
      (node (ref "P1") (pin "G4") (pinfunction "G4_G4") (pintype "passive"))
      (node (ref "P1") (pin "G40") (pinfunction "G40_G40") (pintype "passive"))
      (node (ref "P1") (pin "G5") (pinfunction "G5_G5") (pintype "passive"))
      (node (ref "P1") (pin "G8") (pinfunction "G8_G8") (pintype "passive"))
      (node (ref "P1") (pin "H12") (pinfunction "H12_H12") (pintype "passive"))
      (node (ref "P1") (pin "H15") (pinfunction "H15_H15") (pintype "passive"))
      (node (ref "P1") (pin "H18") (pinfunction "H18_H18") (pintype "passive"))
      (node (ref "P1") (pin "H2") (pinfunction "H2_H2") (pintype "passive"))
      (node (ref "P1") (pin "H21") (pinfunction "H21_H21") (pintype "passive"))
      (node (ref "P1") (pin "H24") (pinfunction "H24_H24") (pintype "passive"))
      (node (ref "P1") (pin "H27") (pinfunction "H27_H27") (pintype "passive"))
      (node (ref "P1") (pin "H3") (pinfunction "H3_H3") (pintype "passive"))
      (node (ref "P1") (pin "H30") (pinfunction "H30_H30") (pintype "passive"))
      (node (ref "P1") (pin "H33") (pinfunction "H33_H33") (pintype "passive"))
      (node (ref "P1") (pin "H36") (pinfunction "H36_H36") (pintype "passive"))
      (node (ref "P1") (pin "H39") (pinfunction "H39_H39") (pintype "passive"))
      (node (ref "P1") (pin "H6") (pinfunction "H6_H6") (pintype "passive"))
      (node (ref "P1") (pin "H9") (pinfunction "H9_H9") (pintype "passive"))
      (node (ref "R23") (pin "2") (pinfunction "2_2") (pintype "passive"))
      (node (ref "R24") (pin "2") (pinfunction "2_2") (pintype "passive"))
      (node (ref "R25") (pin "2") (pinfunction "2_2") (pintype "passive"))
      (node (ref "R26") (pin "2") (pinfunction "2_2") (pintype "passive"))
      (node (ref "R27") (pin "2") (pinfunction "2_2") (pintype "passive"))
      (node (ref "R28") (pin "2") (pinfunction "2_2") (pintype "passive"))
      (node (ref "R29") (pin "1") (pinfunction "1_1") (pintype "passive"))
      (node (ref "R30") (pin "1") (pinfunction "1_1") (pintype "passive"))
      (node (ref "R31") (pin "1") (pinfunction "1_1") (pintype "passive"))
      (node (ref "R32") (pin "1") (pinfunction "1_1") (pintype "passive"))
      (node (ref "U5") (pin "21") (pinfunction "EPAD_21") (pintype "passive"))
      (node (ref "U5") (pin "4") (pinfunction "VIN6_4") (pintype "passive"))
      (node (ref "U5") (pin "5") (pinfunction "VIN7_5") (pintype "passive"))
      (node (ref "U5") (pin "6") (pinfunction "GND1_6") (pintype "passive"))
      (node (ref "U5") (pin "9") (pinfunction "GND_9") (pintype "passive"))
      (node (ref "U6") (pin "3") (pinfunction "E2_3") (pintype "passive"))
      (node (ref "U6") (pin "4") (pinfunction "VSS_4") (pintype "passive"))
      (node (ref "U6") (pin "7") (pinfunction "#WC_7") (pintype "passive"))
    )
    (net (code "76") (name "Net-(C60-Pad1)") (class "Default")
      (node (ref "C60") (pin "1") (pinfunction "1_1") (pintype "passive"))
      (node (ref "P2") (pin "16") (pinfunction "16_16") (pintype "passive"))
    )
    (net (code "77") (name "Net-(DS1-+)") (class "Default")
      (node (ref "DS1") (pin "2") (pinfunction "+_2") (pintype "passive"))
      (node (ref "R13") (pin "1") (pinfunction "1_1") (pintype "passive"))
    )
    (net (code "78") (name "Net-(P1-PadD27)") (class "Default")
      (node (ref "P1") (pin "D27") (pinfunction "D27_D27") (pintype "passive"))
      (node (ref "R14") (pin "1") (pinfunction "1_1") (pintype "passive"))
    )
    (net (code "79") (name "Net-(P1-PadD30)") (class "Default")
      (node (ref "P1") (pin "D30") (pinfunction "D30_D30") (pintype "passive"))
      (node (ref "P1") (pin "D31") (pinfunction "D31_D31") (pintype "passive"))
    )
    (net (code "80") (name "Net-(U5-DCAP)") (class "Default")
      (node (ref "C62") (pin "1") (pinfunction "1_1") (pintype "passive"))
      (node (ref "U5") (pin "8") (pinfunction "DCAP_8") (pintype "passive"))
    )
    (net (code "81") (name "Net-(U5-VIN0)") (class "Default")
      (node (ref "R22") (pin "2") (pinfunction "2_2") (pintype "passive"))
      (node (ref "R28") (pin "1") (pinfunction "1_1") (pintype "passive"))
      (node (ref "U5") (pin "18") (pinfunction "VIN0_18") (pintype "passive"))
    )
    (net (code "82") (name "Net-(U5-VIN1)") (class "Default")
      (node (ref "R21") (pin "2") (pinfunction "2_2") (pintype "passive"))
      (node (ref "R27") (pin "1") (pinfunction "1_1") (pintype "passive"))
      (node (ref "U5") (pin "19") (pinfunction "VIN1_19") (pintype "passive"))
    )
    (net (code "83") (name "Net-(U5-VIN2)") (class "Default")
      (node (ref "R20") (pin "2") (pinfunction "2_2") (pintype "passive"))
      (node (ref "R26") (pin "1") (pinfunction "1_1") (pintype "passive"))
      (node (ref "U5") (pin "20") (pinfunction "VIN2_20") (pintype "passive"))
    )
    (net (code "84") (name "Net-(U5-VIN3)") (class "Default")
      (node (ref "R19") (pin "2") (pinfunction "2_2") (pintype "passive"))
      (node (ref "R25") (pin "1") (pinfunction "1_1") (pintype "passive"))
      (node (ref "U5") (pin "1") (pinfunction "VIN3_1") (pintype "passive"))
    )
    (net (code "85") (name "Net-(U5-VIN4)") (class "Default")
      (node (ref "R18") (pin "2") (pinfunction "2_2") (pintype "passive"))
      (node (ref "R24") (pin "1") (pinfunction "1_1") (pintype "passive"))
      (node (ref "U5") (pin "2") (pinfunction "VIN4_2") (pintype "passive"))
    )
    (net (code "86") (name "Net-(U5-VIN5)") (class "Default")
      (node (ref "R17") (pin "2") (pinfunction "2_2") (pintype "passive"))
      (node (ref "R23") (pin "1") (pinfunction "1_1") (pintype "passive"))
      (node (ref "U5") (pin "3") (pinfunction "VIN5_3") (pintype "passive"))
    )
    (net (code "87") (name "Net-(U5-VREF)") (class "Default")
      (node (ref "C61") (pin "2") (pinfunction "2_2") (pintype "passive"))
      (node (ref "U5") (pin "7") (pinfunction "VREF_7") (pintype "passive"))
    )
    (net (code "88") (name "VDD_INTERFACE") (class "Default")
      (node (ref "R12") (pin "2") (pinfunction "2_2") (pintype "passive"))
      (node (ref "R18") (pin "1") (pinfunction "1_1") (pintype "passive"))
      (node (ref "TP243") (pin "1") (pinfunction "TP_1") (pintype "passive"))
    )
    (net (code "89") (name "unconnected-(P1-PadC2)") (class "Default")
      (node (ref "P1") (pin "C2") (pinfunction "C2_C2") (pintype "passive+no_connect"))
    )
    (net (code "90") (name "unconnected-(P1-PadC3)") (class "Default")
      (node (ref "P1") (pin "C3") (pinfunction "C3_C3") (pintype "passive+no_connect"))
    )
    (net (code "91") (name "unconnected-(P1-PadC6)") (class "Default")
      (node (ref "P1") (pin "C6") (pinfunction "C6_C6") (pintype "passive+no_connect"))
    )
    (net (code "92") (name "unconnected-(P1-PadC7)") (class "Default")
      (node (ref "P1") (pin "C7") (pinfunction "C7_C7") (pintype "passive+no_connect"))
    )
    (net (code "93") (name "unconnected-(P1-PadC22)") (class "Default")
      (node (ref "P1") (pin "C22") (pinfunction "C22_C22") (pintype "passive+no_connect"))
    )
    (net (code "94") (name "unconnected-(P1-PadC23)") (class "Default")
      (node (ref "P1") (pin "C23") (pinfunction "C23_C23") (pintype "passive+no_connect"))
    )
    (net (code "95") (name "unconnected-(P1-PadD4)") (class "Default")
      (node (ref "P1") (pin "D4") (pinfunction "D4_D4") (pintype "passive+no_connect"))
    )
    (net (code "96") (name "unconnected-(P1-PadD5)") (class "Default")
      (node (ref "P1") (pin "D5") (pinfunction "D5_D5") (pintype "passive+no_connect"))
    )
    (net (code "97") (name "unconnected-(P1-PadD20)") (class "Default")
      (node (ref "P1") (pin "D20") (pinfunction "D20_D20") (pintype "passive+no_connect"))
    )
    (net (code "98") (name "unconnected-(P1-PadD21)") (class "Default")
      (node (ref "P1") (pin "D21") (pinfunction "D21_D21") (pintype "passive+no_connect"))
    )
    (net (code "99") (name "unconnected-(P1-PadD29)") (class "Default")
      (node (ref "P1") (pin "D29") (pinfunction "D29_D29") (pintype "passive+no_connect"))
    )
    (net (code "100") (name "unconnected-(P1-PadD33)") (class "Default")
      (node (ref "P1") (pin "D33") (pinfunction "D33_D33") (pintype "passive+no_connect"))
    )
    (net (code "101") (name "unconnected-(P1-PadD34)") (class "Default")
      (node (ref "P1") (pin "D34") (pinfunction "D34_D34") (pintype "passive+no_connect"))
    )
    (net (code "102") (name "unconnected-(P1-PadG2)") (class "Default")
      (node (ref "P1") (pin "G2") (pinfunction "G2_G2") (pintype "passive+no_connect"))
    )
    (net (code "103") (name "unconnected-(P1-PadG3)") (class "Default")
      (node (ref "P1") (pin "G3") (pinfunction "G3_G3") (pintype "passive+no_connect"))
    )
    (net (code "104") (name "unconnected-(P1-PadG30)") (class "Default")
      (node (ref "P1") (pin "G30") (pinfunction "G30_G30") (pintype "passive+no_connect"))
    )
    (net (code "105") (name "unconnected-(P1-PadG31)") (class "Default")
      (node (ref "P1") (pin "G31") (pinfunction "G31_G31") (pintype "passive+no_connect"))
    )
    (net (code "106") (name "unconnected-(P1-PadG33)") (class "Default")
      (node (ref "P1") (pin "G33") (pinfunction "G33_G33") (pintype "passive+no_connect"))
    )
    (net (code "107") (name "unconnected-(P1-PadG34)") (class "Default")
      (node (ref "P1") (pin "G34") (pinfunction "G34_G34") (pintype "passive+no_connect"))
    )
    (net (code "108") (name "unconnected-(P1-PadG36)") (class "Default")
      (node (ref "P1") (pin "G36") (pinfunction "G36_G36") (pintype "passive+no_connect"))
    )
    (net (code "109") (name "unconnected-(P1-PadG37)") (class "Default")
      (node (ref "P1") (pin "G37") (pinfunction "G37_G37") (pintype "passive+no_connect"))
    )
    (net (code "110") (name "unconnected-(P1-PadH1)") (class "Default")
      (node (ref "P1") (pin "H1") (pinfunction "H1_H1") (pintype "passive+no_connect"))
    )
    (net (code "111") (name "unconnected-(P1-PadH5)") (class "Default")
      (node (ref "P1") (pin "H5") (pinfunction "H5_H5") (pintype "passive+no_connect"))
    )
    (net (code "112") (name "unconnected-(P1-PadH32)") (class "Default")
      (node (ref "P1") (pin "H32") (pinfunction "H32_H32") (pintype "passive+no_connect"))
    )
    (net (code "113") (name "unconnected-(P1-PadH34)") (class "Default")
      (node (ref "P1") (pin "H34") (pinfunction "H34_H34") (pintype "passive+no_connect"))
    )
    (net (code "114") (name "unconnected-(P1-PadH35)") (class "Default")
      (node (ref "P1") (pin "H35") (pinfunction "H35_H35") (pintype "passive+no_connect"))
    )
    (net (code "115") (name "unconnected-(P1-PadH37)") (class "Default")
      (node (ref "P1") (pin "H37") (pinfunction "H37_H37") (pintype "passive+no_connect"))
    )
    (net (code "116") (name "unconnected-(P1-PadH38)") (class "Default")
      (node (ref "P1") (pin "H38") (pinfunction "H38_H38") (pintype "passive+no_connect"))
    )
    (net (code "117") (name "unconnected-(U5-ALERT-Pad12)") (class "Default")
      (node (ref "U5") (pin "12") (pinfunction "ALERT_12") (pintype "passive+no_connect"))
    )
  )
)
